# untitled.net
KiCad netlist of a schematic drawn in EAGLE
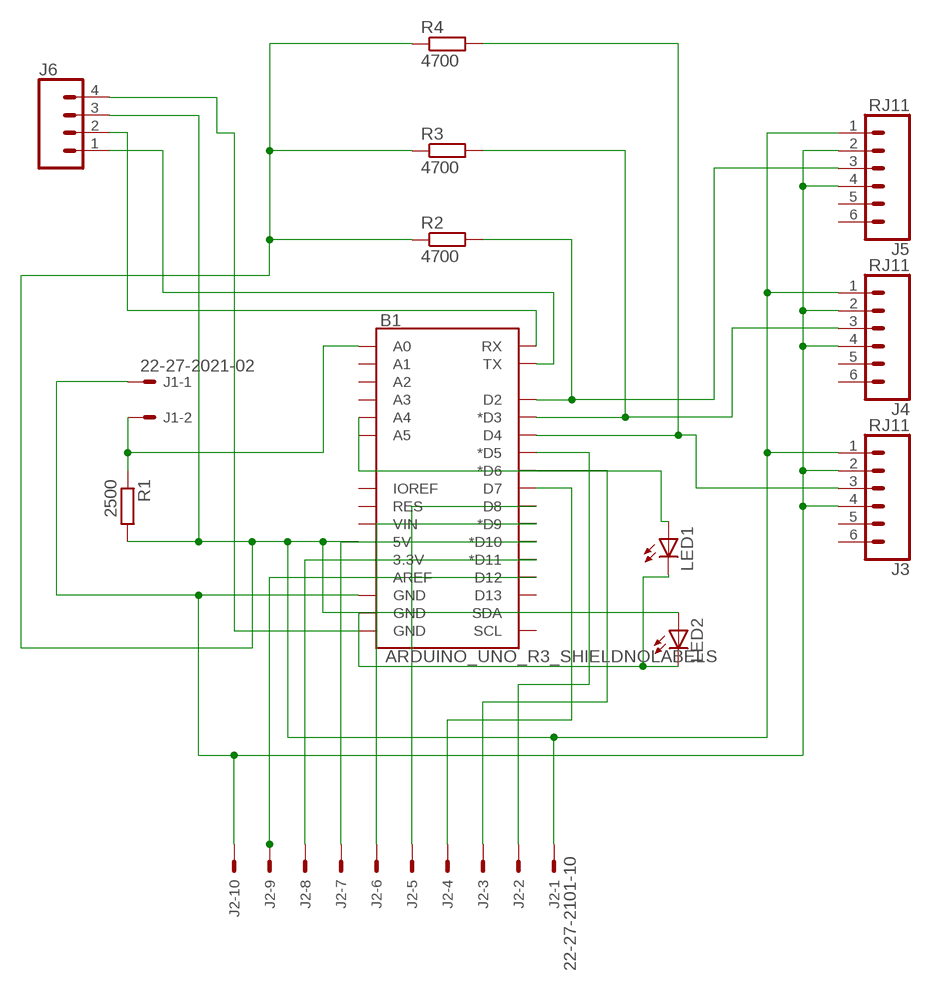
[diagram p0: schematic, sheet 1]

(export (version "E")
  (design (tool "Eeschema 10.0.6"))
  (components
    (comp (ref "B1")
      (value "ARDUINO_UNO_R3_SHIELDNOLABELS")
      (footprint "eagle-import:UNO_R3_SHIELD_NOLABELS")
      (libsource (lib "eagle-import") (part "ARDUINO_UNO_R3_SHIELDNOLABELS"))
    )
    (comp (ref "J1")
      (value "22-27-2021-02")
      (footprint "eagle-import:6410-02")
      (libsource (lib "eagle-import") (part "22-?-0227-2021"))
    )
    (comp (ref "J2")
      (value "22-27-2101-10")
      (footprint "eagle-import:6410-10")
      (libsource (lib "eagle-import") (part "22-?-1027-2101"))
    )
    (comp (ref "J3")
      (value "RJ11")
      (footprint "eagle-import:RJ11-6")
      (libsource (lib "eagle-import") (part "RJ11-6"))
    )
    (comp (ref "J4")
      (value "RJ11")
      (footprint "eagle-import:RJ11-6")
      (libsource (lib "eagle-import") (part "RJ11-6"))
    )
    (comp (ref "J5")
      (value "RJ11")
      (footprint "eagle-import:RJ11-6")
      (libsource (lib "eagle-import") (part "RJ11-6"))
    )
    (comp (ref "J6")
      (value "CONN_04")
      (footprint "eagle-import:1X04")
      (libsource (lib "eagle-import") (part "CONN_04"))
    )
    (comp (ref "LED1")
      (value "LED3MM")
      (footprint "eagle-import:LED3MM")
      (libsource (lib "eagle-import") (part "LED3MM"))
    )
    (comp (ref "LED2")
      (value "LED3MM")
      (footprint "eagle-import:LED3MM")
      (libsource (lib "eagle-import") (part "LED3MM"))
    )
    (comp (ref "R1")
      (value "2500")
      (footprint "eagle-import:R1206")
      (libsource (lib "eagle-import") (part "R-EU_R1206"))
    )
    (comp (ref "R2")
      (value "4700")
      (footprint "eagle-import:R1206")
      (libsource (lib "eagle-import") (part "R-EU_R1206"))
    )
    (comp (ref "R3")
      (value "4700")
      (footprint "eagle-import:R1206")
      (libsource (lib "eagle-import") (part "R-EU_R1206"))
    )
    (comp (ref "R4")
      (value "4700")
      (footprint "eagle-import:R1206")
      (libsource (lib "eagle-import") (part "R-EU_R1206"))
    )
  )
  (nets
    (net (code "1") (name "Net-(B1-*D3)") (class "Default")
      (node (ref "B1") (pin "D3") (pinfunction "*D3_D3") (pintype "bidirectional"))
      (node (ref "J4") (pin "3") (pinfunction "3_3") (pintype "passive"))
      (node (ref "R3") (pin "2") (pinfunction "2_2") (pintype "passive"))
    )
    (net (code "2") (name "Net-(B1-*D5)") (class "Default")
      (node (ref "B1") (pin "D5") (pinfunction "*D5_D5") (pintype "bidirectional"))
      (node (ref "J2") (pin "2") (pinfunction "S_2") (pintype "passive"))
    )
    (net (code "3") (name "Net-(B1-*D6)") (class "Default")
      (node (ref "B1") (pin "D6") (pinfunction "*D6_D6") (pintype "bidirectional"))
      (node (ref "J2") (pin "3") (pinfunction "S_3") (pintype "passive"))
    )
    (net (code "4") (name "Net-(B1-*D9)") (class "Default")
      (node (ref "B1") (pin "D9") (pinfunction "*D9_D9") (pintype "bidirectional"))
      (node (ref "J2") (pin "6") (pinfunction "S_6") (pintype "passive"))
    )
    (net (code "5") (name "Net-(B1-*D10)") (class "Default")
      (node (ref "B1") (pin "D10") (pinfunction "*D10_D10") (pintype "bidirectional"))
      (node (ref "J2") (pin "7") (pinfunction "S_7") (pintype "passive"))
    )
    (net (code "6") (name "Net-(B1-*D11)") (class "Default")
      (node (ref "B1") (pin "D11") (pinfunction "*D11_D11") (pintype "bidirectional"))
      (node (ref "J2") (pin "8") (pinfunction "S_8") (pintype "passive"))
    )
    (net (code "7") (name "Net-(B1-GND-PadGND@0)") (class "Default")
      (node (ref "B1") (pin "GND@0") (pinfunction "GND_GND@0") (pintype "bidirectional"))
      (node (ref "J6") (pin "4") (pinfunction "4_4") (pintype "passive"))
    )
    (net (code "8") (name "Net-(B1-PadA4)") (class "Default")
      (node (ref "B1") (pin "A4") (pinfunction "A4_A4") (pintype "bidirectional"))
      (node (ref "LED1") (pin "A") (pinfunction "A_A") (pintype "passive"))
    )
    (net (code "9") (name "Net-(B1-PadD2)") (class "Default")
      (node (ref "B1") (pin "D2") (pinfunction "D2_D2") (pintype "bidirectional"))
      (node (ref "J5") (pin "3") (pinfunction "3_3") (pintype "passive"))
      (node (ref "R2") (pin "2") (pinfunction "2_2") (pintype "passive"))
    )
    (net (code "10") (name "Net-(B1-PadD4)") (class "Default")
      (node (ref "B1") (pin "D4") (pinfunction "D4_D4") (pintype "bidirectional"))
      (node (ref "J3") (pin "3") (pinfunction "3_3") (pintype "passive"))
      (node (ref "R4") (pin "2") (pinfunction "2_2") (pintype "passive"))
    )
    (net (code "11") (name "Net-(B1-PadRX)") (class "Default")
      (node (ref "B1") (pin "RX") (pinfunction "RX_RX") (pintype "bidirectional"))
      (node (ref "J6") (pin "2") (pinfunction "2_2") (pintype "passive"))
    )
    (net (code "12") (name "Net-(B1-PadTX)") (class "Default")
      (node (ref "B1") (pin "TX") (pinfunction "TX_TX") (pintype "bidirectional"))
      (node (ref "J6") (pin "1") (pinfunction "1_1") (pintype "passive"))
    )
    (net (code "13") (name "Net-(J1A-S)") (class "Default")
      (node (ref "B1") (pin "GND@2") (pinfunction "GND_GND@2") (pintype "bidirectional"))
      (node (ref "J1") (pin "1") (pinfunction "S_1") (pintype "passive"))
      (node (ref "J2") (pin "10") (pinfunction "S_10") (pintype "passive"))
      (node (ref "J3") (pin "2") (pinfunction "2_2") (pintype "passive"))
      (node (ref "J3") (pin "4") (pinfunction "4_4") (pintype "passive"))
      (node (ref "J4") (pin "2") (pinfunction "2_2") (pintype "passive"))
      (node (ref "J4") (pin "4") (pinfunction "4_4") (pintype "passive"))
      (node (ref "J5") (pin "2") (pinfunction "2_2") (pintype "passive"))
      (node (ref "J5") (pin "4") (pinfunction "4_4") (pintype "passive"))
    )
    (net (code "14") (name "Net-(J1B-S)") (class "Default")
      (node (ref "B1") (pin "A0") (pinfunction "A0_A0") (pintype "bidirectional"))
      (node (ref "J1") (pin "2") (pinfunction "S_2") (pintype "passive"))
      (node (ref "R1") (pin "1") (pinfunction "1_1") (pintype "passive"))
    )
    (net (code "15") (name "Net-(J2A-S)") (class "Default")
      (node (ref "B1") (pin "5V") (pinfunction "5V_5V") (pintype "bidirectional"))
      (node (ref "J2") (pin "1") (pinfunction "S_1") (pintype "passive"))
      (node (ref "J3") (pin "1") (pinfunction "1_1") (pintype "passive"))
      (node (ref "J4") (pin "1") (pinfunction "1_1") (pintype "passive"))
      (node (ref "J5") (pin "1") (pinfunction "1_1") (pintype "passive"))
      (node (ref "J6") (pin "3") (pinfunction "3_3") (pintype "passive"))
      (node (ref "LED2") (pin "A") (pinfunction "A_A") (pintype "passive"))
      (node (ref "R1") (pin "2") (pinfunction "2_2") (pintype "passive"))
      (node (ref "R2") (pin "1") (pinfunction "1_1") (pintype "passive"))
      (node (ref "R3") (pin "1") (pinfunction "1_1") (pintype "passive"))
      (node (ref "R4") (pin "1") (pinfunction "1_1") (pintype "passive"))
    )
    (net (code "16") (name "Net-(J2E-S)") (class "Default")
      (node (ref "B1") (pin "D7") (pinfunction "D7_D7") (pintype "bidirectional"))
      (node (ref "J2") (pin "4") (pinfunction "S_4") (pintype "passive"))
    )
    (net (code "17") (name "Net-(J2F-S)") (class "Default")
      (node (ref "B1") (pin "D8") (pinfunction "D8_D8") (pintype "bidirectional"))
      (node (ref "J2") (pin "5") (pinfunction "S_5") (pintype "passive"))
    )
    (net (code "18") (name "Net-(J2J-S)") (class "Default")
      (node (ref "B1") (pin "D12") (pinfunction "D12_D12") (pintype "bidirectional"))
      (node (ref "J2") (pin "9") (pinfunction "S_9") (pintype "passive"))
    )
    (net (code "19") (name "Net-(LED1-C)") (class "Default")
      (node (ref "B1") (pin "GND@1") (pinfunction "GND_GND@1") (pintype "bidirectional"))
      (node (ref "LED1") (pin "K") (pinfunction "C_K") (pintype "passive"))
      (node (ref "LED2") (pin "K") (pinfunction "C_K") (pintype "passive"))
    )
    (net (code "20") (name "unconnected-(B1-Pad3.3V)") (class "Default")
      (node (ref "B1") (pin "3.3V") (pinfunction "3.3V_3.3V") (pintype "bidirectional"))
    )
    (net (code "21") (name "unconnected-(B1-PadA1)") (class "Default")
      (node (ref "B1") (pin "A1") (pinfunction "A1_A1") (pintype "bidirectional"))
    )
    (net (code "22") (name "unconnected-(B1-PadA2)") (class "Default")
      (node (ref "B1") (pin "A2") (pinfunction "A2_A2") (pintype "bidirectional"))
    )
    (net (code "23") (name "unconnected-(B1-PadA3)") (class "Default")
      (node (ref "B1") (pin "A3") (pinfunction "A3_A3") (pintype "bidirectional"))
    )
    (net (code "24") (name "unconnected-(B1-PadA5)") (class "Default")
      (node (ref "B1") (pin "A5") (pinfunction "A5_A5") (pintype "bidirectional"))
    )
    (net (code "25") (name "unconnected-(B1-PadAREF)") (class "Default")
      (node (ref "B1") (pin "AREF") (pinfunction "AREF_AREF") (pintype "bidirectional"))
    )
    (net (code "26") (name "unconnected-(B1-PadD13)") (class "Default")
      (node (ref "B1") (pin "D13") (pinfunction "D13_D13") (pintype "bidirectional"))
    )
    (net (code "27") (name "unconnected-(B1-PadIOREF)") (class "Default")
      (node (ref "B1") (pin "IOREF") (pinfunction "IOREF_IOREF") (pintype "bidirectional"))
    )
    (net (code "28") (name "unconnected-(B1-PadRES)") (class "Default")
      (node (ref "B1") (pin "RES") (pinfunction "RES_RES") (pintype "bidirectional"))
    )
    (net (code "29") (name "unconnected-(B1-PadSCL)") (class "Default")
      (node (ref "B1") (pin "SCL") (pinfunction "SCL_SCL") (pintype "bidirectional"))
    )
    (net (code "30") (name "unconnected-(B1-PadSDA)") (class "Default")
      (node (ref "B1") (pin "SDA") (pinfunction "SDA_SDA") (pintype "bidirectional"))
    )
    (net (code "31") (name "unconnected-(B1-PadVIN)") (class "Default")
      (node (ref "B1") (pin "VIN") (pinfunction "VIN_VIN") (pintype "bidirectional"))
    )
    (net (code "32") (name "unconnected-(J3-Pad5)") (class "Default")
      (node (ref "J3") (pin "5") (pinfunction "5_5") (pintype "passive"))
    )
    (net (code "33") (name "unconnected-(J3-Pad6)") (class "Default")
      (node (ref "J3") (pin "6") (pinfunction "6_6") (pintype "passive"))
    )
    (net (code "34") (name "unconnected-(J4-Pad5)") (class "Default")
      (node (ref "J4") (pin "5") (pinfunction "5_5") (pintype "passive"))
    )
    (net (code "35") (name "unconnected-(J4-Pad6)") (class "Default")
      (node (ref "J4") (pin "6") (pinfunction "6_6") (pintype "passive"))
    )
    (net (code "36") (name "unconnected-(J5-Pad5)") (class "Default")
      (node (ref "J5") (pin "5") (pinfunction "5_5") (pintype "passive"))
    )
    (net (code "37") (name "unconnected-(J5-Pad6)") (class "Default")
      (node (ref "J5") (pin "6") (pinfunction "6_6") (pintype "passive"))
    )
  )
)
